# 2x6x1_27mm-pogo-adapter-mk-1_0_0.net
KiCad netlist of a schematic drawn in EAGLE
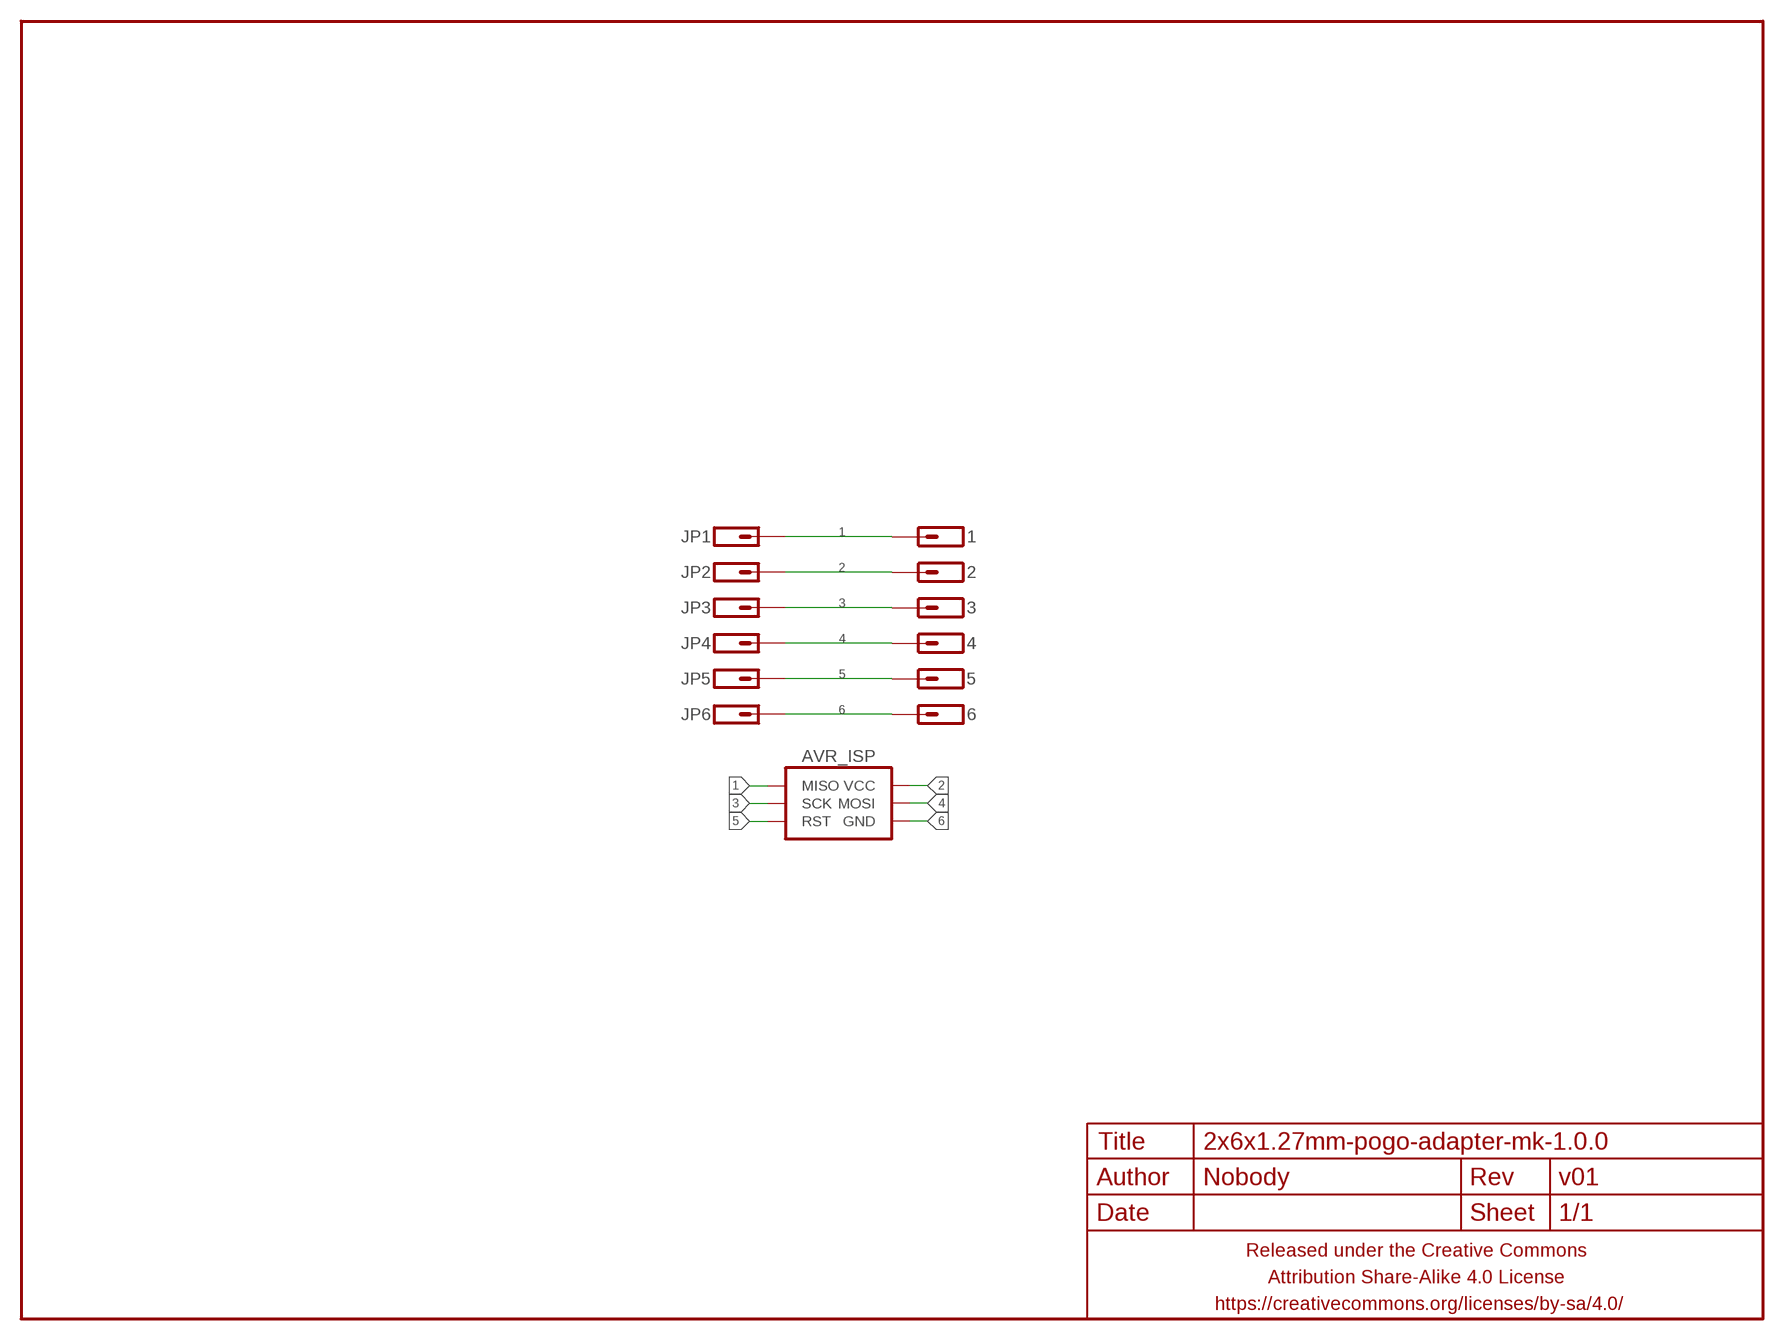
[diagram p0: schematic, sheet 1]

(export (version "E")
  (design (tool "Eeschema 10.0.6"))
  (components
    (comp (ref "1")
      (value "M01PTH")
      (footprint "eagle-import:1X01")
      (libsource (lib "eagle-import") (part "M01PTH"))
    )
    (comp (ref "2")
      (value "M01PTH")
      (footprint "eagle-import:1X01")
      (libsource (lib "eagle-import") (part "M01PTH"))
    )
    (comp (ref "3")
      (value "M01PTH")
      (footprint "eagle-import:1X01")
      (libsource (lib "eagle-import") (part "M01PTH"))
    )
    (comp (ref "4")
      (value "M01PTH")
      (footprint "eagle-import:1X01")
      (libsource (lib "eagle-import") (part "M01PTH"))
    )
    (comp (ref "5")
      (value "M01PTH")
      (footprint "eagle-import:1X01")
      (libsource (lib "eagle-import") (part "M01PTH"))
    )
    (comp (ref "6")
      (value "M01PTH")
      (footprint "eagle-import:1X01")
      (libsource (lib "eagle-import") (part "M01PTH"))
    )
    (comp (ref "AVR_ISP")
      (value "AVR_SPI_PRG_6PTH-SHROUD-ALT")
      (footprint "eagle-import:2X3-SHROUDED-ALT")
      (libsource (lib "eagle-import") (part "AVR_SPI_PRG_6PTH-SHROUD-ALT"))
    )
    (comp (ref "FRAME1")
      (value "FRAME-LETTERNO_PACKAGE")
      (footprint "eagle-import:DUMMY")
      (fields (field (name "DESIGNER") "Nobody") (field (name "VERSION") "v01"))
      (libsource (lib "eagle-import") (part "FRAME-LETTERNO_PACKAGE"))
    )
    (comp (ref "JP1")
      (value "M01PTH-0.7MM-CIR-NS")
      (footprint "eagle-import:1X01-0.7MM-CIR-NS")
      (libsource (lib "eagle-import") (part "M01PTH-0.7MM-CIR-NS"))
    )
    (comp (ref "JP2")
      (value "M01PTH-0.65MM-NS")
      (footprint "eagle-import:1X01_635MM")
      (libsource (lib "eagle-import") (part "M01PTH-0.65MM-NS"))
    )
    (comp (ref "JP3")
      (value "M01PTH-0.65MM-NS")
      (footprint "eagle-import:1X01_635MM")
      (libsource (lib "eagle-import") (part "M01PTH-0.65MM-NS"))
    )
    (comp (ref "JP4")
      (value "M01PTH-0.65MM-NS")
      (footprint "eagle-import:1X01_635MM")
      (libsource (lib "eagle-import") (part "M01PTH-0.65MM-NS"))
    )
    (comp (ref "JP5")
      (value "M01PTH-0.65MM-NS")
      (footprint "eagle-import:1X01_635MM")
      (libsource (lib "eagle-import") (part "M01PTH-0.65MM-NS"))
    )
    (comp (ref "JP6")
      (value "M01PTH-0.65MM-NS")
      (footprint "eagle-import:1X01_635MM")
      (libsource (lib "eagle-import") (part "M01PTH-0.65MM-NS"))
    )
  )
  (nets
    (net (code "1") (name "1") (class "Default")
      (node (ref "1") (pin "1") (pinfunction "1_1") (pintype "passive"))
      (node (ref "AVR_ISP") (pin "1") (pinfunction "MISO_1") (pintype "passive"))
      (node (ref "JP1") (pin "P$1") (pinfunction "1_P$1") (pintype "passive"))
    )
    (net (code "2") (name "2") (class "Default")
      (node (ref "2") (pin "1") (pinfunction "1_1") (pintype "passive"))
      (node (ref "AVR_ISP") (pin "2") (pinfunction "VCC_2") (pintype "passive"))
      (node (ref "JP2") (pin "P$1") (pinfunction "1_P$1") (pintype "passive"))
    )
    (net (code "3") (name "3") (class "Default")
      (node (ref "3") (pin "1") (pinfunction "1_1") (pintype "passive"))
      (node (ref "AVR_ISP") (pin "3") (pinfunction "SCK_3") (pintype "passive"))
      (node (ref "JP3") (pin "P$1") (pinfunction "1_P$1") (pintype "passive"))
    )
    (net (code "4") (name "4") (class "Default")
      (node (ref "4") (pin "1") (pinfunction "1_1") (pintype "passive"))
      (node (ref "AVR_ISP") (pin "4") (pinfunction "MOSI_4") (pintype "passive"))
      (node (ref "JP4") (pin "P$1") (pinfunction "1_P$1") (pintype "passive"))
    )
    (net (code "5") (name "5") (class "Default")
      (node (ref "5") (pin "1") (pinfunction "1_1") (pintype "passive"))
      (node (ref "AVR_ISP") (pin "5") (pinfunction "RST_5") (pintype "passive"))
      (node (ref "JP5") (pin "P$1") (pinfunction "1_P$1") (pintype "passive"))
    )
    (net (code "6") (name "6") (class "Default")
      (node (ref "6") (pin "1") (pinfunction "1_1") (pintype "passive"))
      (node (ref "AVR_ISP") (pin "6") (pinfunction "GND_6") (pintype "passive"))
      (node (ref "JP6") (pin "P$1") (pinfunction "1_P$1") (pintype "passive"))
    )
  )
)
